# Peripherals_-_MyoSensor.net
KiCad netlist of a schematic drawn in Altium Designer
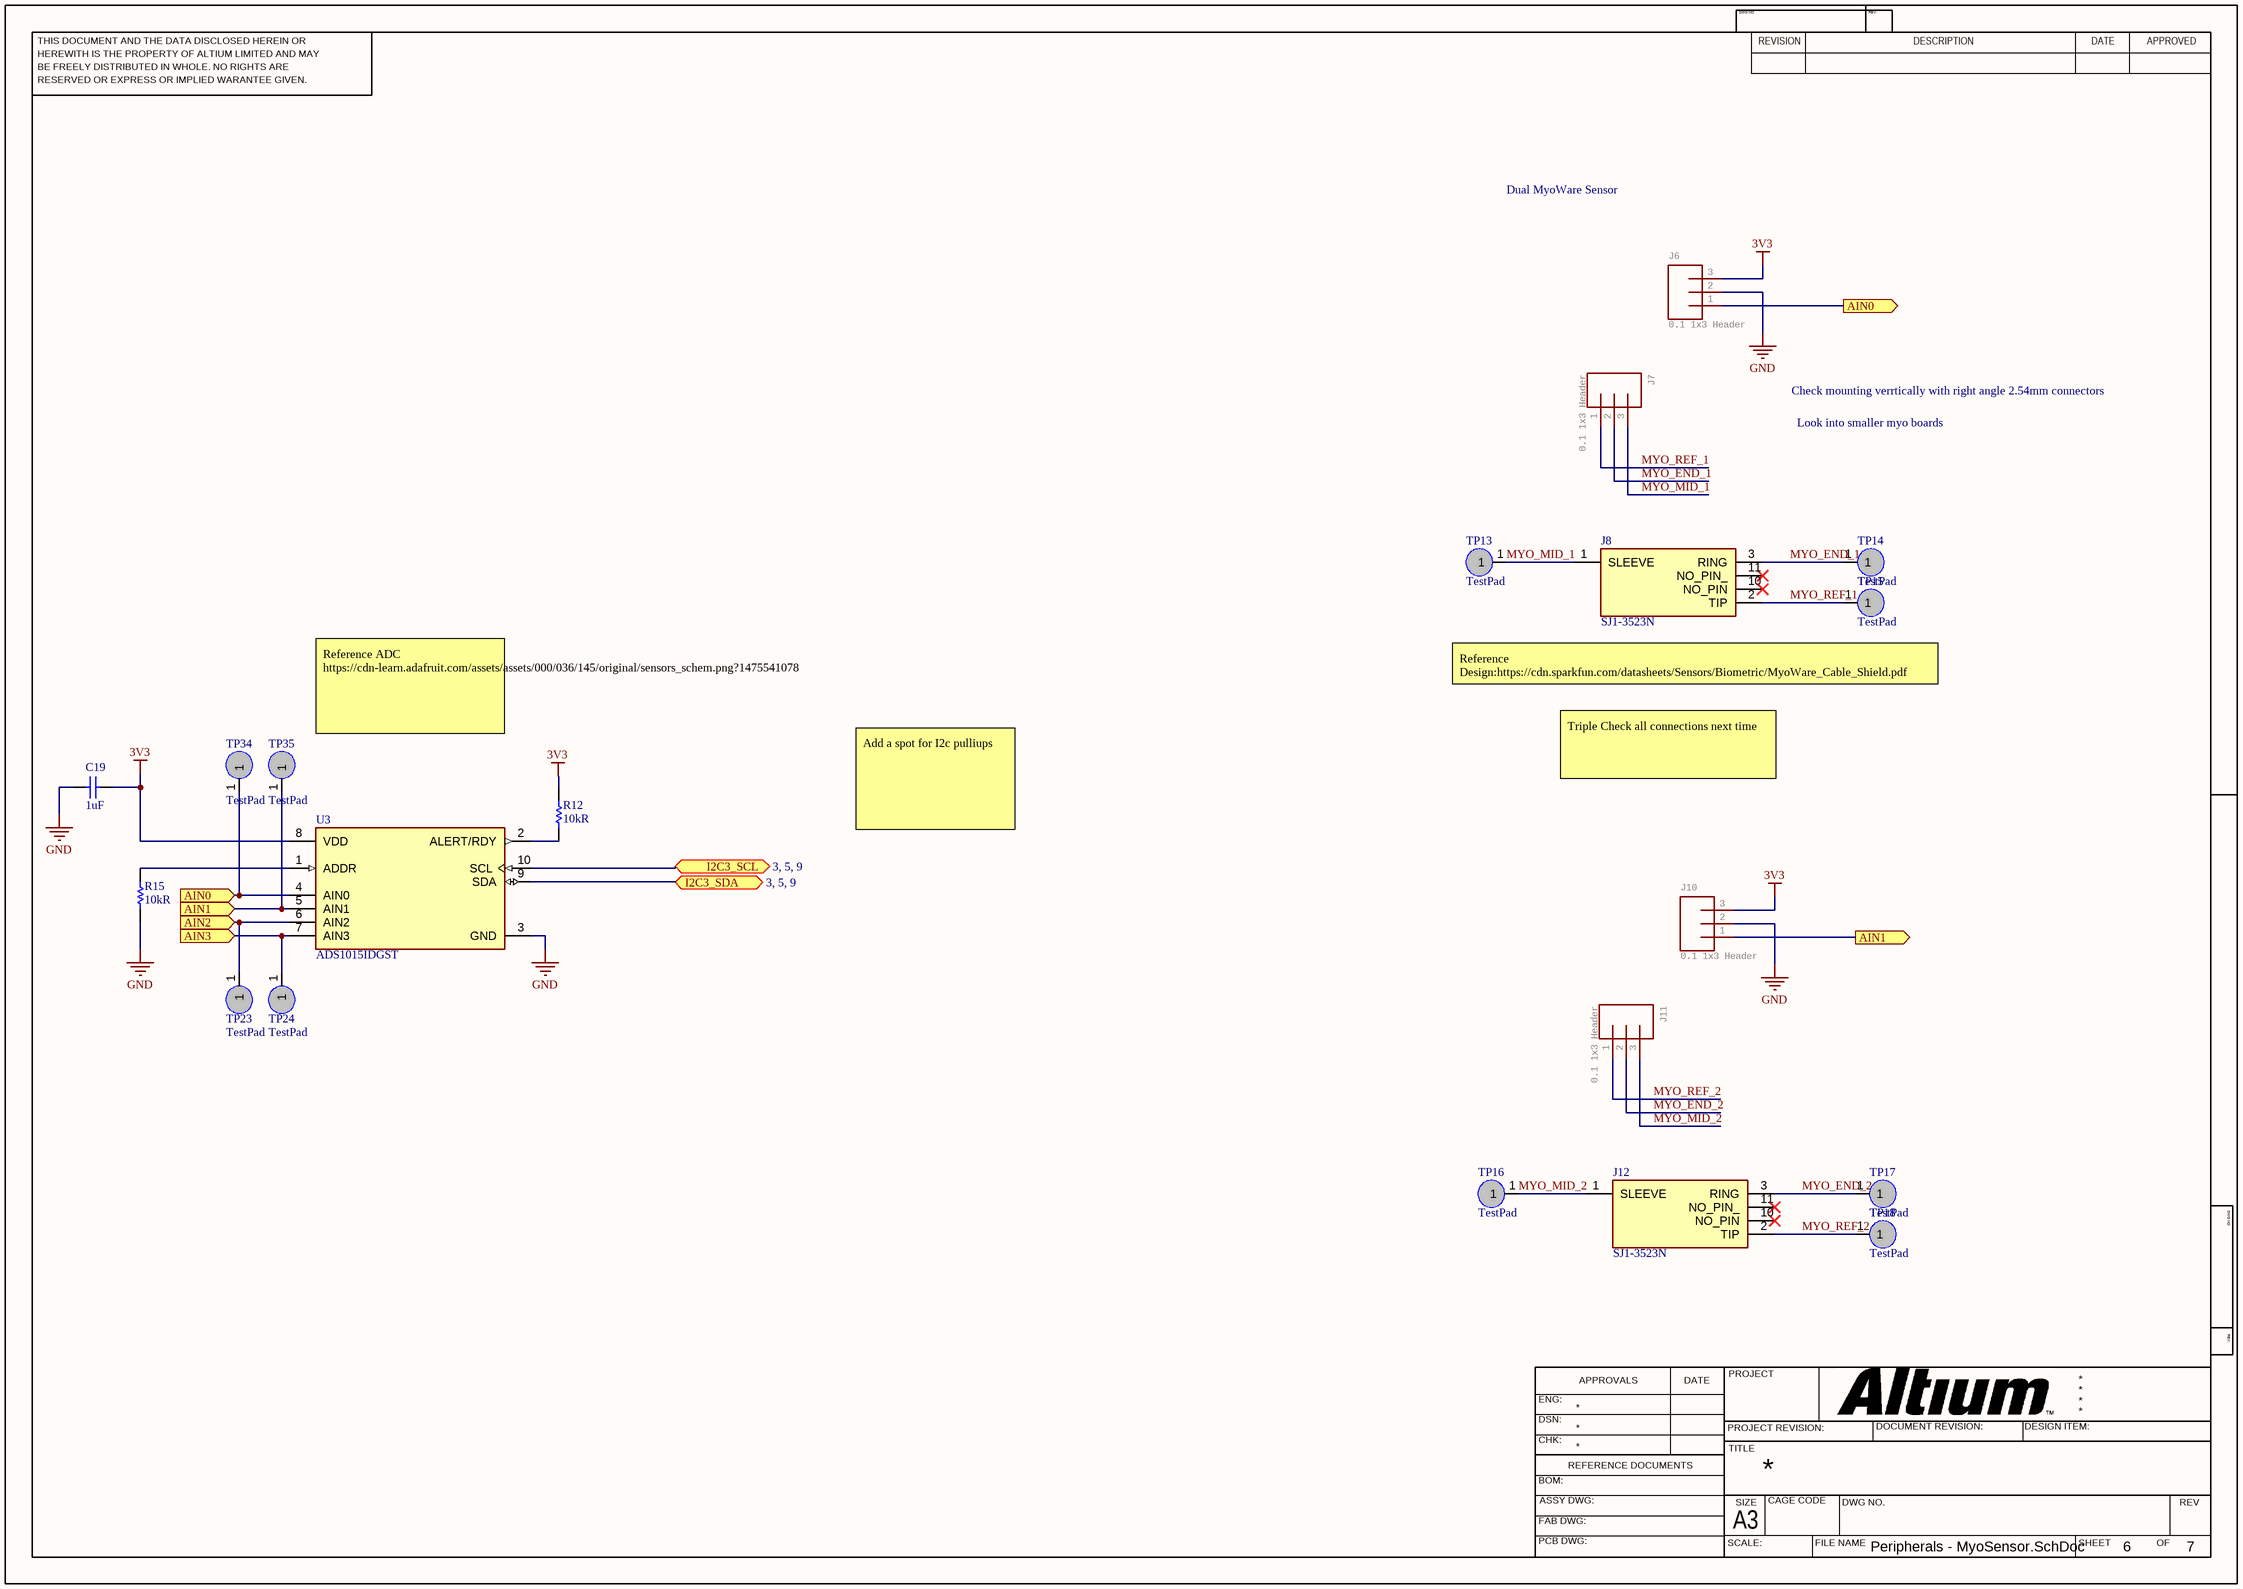
[diagram p0: Peripherals - MyoSensor.SchDoc]

(export (version "E")
  (design (tool "Eeschema 10.0.6"))
  (components
    (comp (ref "C19")
      (value "1uF")
      (footprint "CAPC2013X145X50LL20T25")
      (description "C0805C105K4PACTU")
      (fields (field (name "MANUFACTURER") "Kemet"))
      (libsource (lib "Altium Content Vault") (part "CAP"))
    )
    (comp (ref "J6")
      (value "0.1 1x3 Header")
      (footprint "1X03")
      (libsource (lib "SparkFun-Connectors.Library") (part "CONN_03"))
    )
    (comp (ref "J7")
      (value "0.1 1x3 Header")
      (footprint "1X03")
      (libsource (lib "SparkFun-Connectors.Library") (part "CONN_03"))
    )
    (comp (ref "J8")
      (value "SJ1-3523N")
      (footprint "LayoutFootprintsGoogle:SJ13523N")
      (description "Connector")
      (fields (field (name "MOUSER PART NUMBER") "490-SJ1-3523N"))
      (libsource (lib "*") (part "SJ1-3523N"))
    )
    (comp (ref "J10")
      (value "0.1 1x3 Header")
      (footprint "1X03")
      (libsource (lib "SparkFun-Connectors.Library") (part "CONN_03"))
    )
    (comp (ref "J11")
      (value "0.1 1x3 Header")
      (footprint "1X03")
      (libsource (lib "SparkFun-Connectors.Library") (part "CONN_03"))
    )
    (comp (ref "J12")
      (value "SJ1-3523N")
      (footprint "LayoutFootprintsGoogle:SJ13523N")
      (description "Connector")
      (fields (field (name "MOUSER PART NUMBER") "490-SJ1-3523N"))
      (libsource (lib "*") (part "SJ1-3523N"))
    )
    (comp (ref "R12")
      (value "10kR")
      (footprint "RESC2013X60X35NL10T20")
      (fields (field (name "MANUFACTURER") "Yageo"))
      (libsource (lib "Altium Content Vault") (part "RES-2"))
    )
    (comp (ref "R15")
      (value "10kR")
      (footprint "RESC2013X60X35NL10T20")
      (fields (field (name "MANUFACTURER") "Yageo"))
      (libsource (lib "Altium Content Vault") (part "RES-2"))
    )
    (comp (ref "TP13")
      (value "TestPad")
      (footprint "TestPad50mil")
      (libsource (lib "SchemSymbolsGoogle") (part "TestPad"))
    )
    (comp (ref "TP14")
      (value "TestPad")
      (footprint "TestPad50mil")
      (libsource (lib "SchemSymbolsGoogle") (part "TestPad"))
    )
    (comp (ref "TP15")
      (value "TestPad")
      (footprint "TestPad50mil")
      (libsource (lib "SchemSymbolsGoogle") (part "TestPad"))
    )
    (comp (ref "TP16")
      (value "TestPad")
      (footprint "TestPad50mil")
      (libsource (lib "SchemSymbolsGoogle") (part "TestPad"))
    )
    (comp (ref "TP17")
      (value "TestPad")
      (footprint "TestPad50mil")
      (libsource (lib "SchemSymbolsGoogle") (part "TestPad"))
    )
    (comp (ref "TP18")
      (value "TestPad")
      (footprint "TestPad50mil")
      (libsource (lib "SchemSymbolsGoogle") (part "TestPad"))
    )
    (comp (ref "TP23")
      (value "TestPad")
      (footprint "TestPad50mil")
      (libsource (lib "SchemSymbolsGoogle") (part "TestPad"))
    )
    (comp (ref "TP24")
      (value "TestPad")
      (footprint "TestPad50mil")
      (libsource (lib "SchemSymbolsGoogle") (part "TestPad"))
    )
    (comp (ref "TP34")
      (value "TestPad")
      (footprint "TestPad50mil")
      (libsource (lib "SchemSymbolsGoogle") (part "TestPad"))
    )
    (comp (ref "TP35")
      (value "TestPad")
      (footprint "TestPad50mil")
      (libsource (lib "SchemSymbolsGoogle") (part "TestPad"))
    )
    (comp (ref "U3")
      (value "ADS1015IDGST")
      (footprint "FP-DGS0010A-MFG")
      (description "IC ADC 12BIT SIGMA-DELTA 10VSSOP")
      (libsource (lib "Altium Content Vault") (part "0fb225032f4bd54fd540a872e776a50"))
    )
  )
  (nets
    (net (code "1") (name "/AIN0") (class "Default")
      (node (ref "J6") (pin "1") (pinfunction "1_1") (pintype "passive"))
      (node (ref "TP34") (pin "1") (pinfunction "1_1") (pintype "passive"))
      (node (ref "U3") (pin "4") (pinfunction "AIN0_4") (pintype "passive"))
    )
    (net (code "2") (name "/AIN1") (class "Default")
      (node (ref "J10") (pin "1") (pinfunction "1_1") (pintype "passive"))
      (node (ref "TP35") (pin "1") (pinfunction "1_1") (pintype "passive"))
      (node (ref "U3") (pin "5") (pinfunction "AIN1_5") (pintype "passive"))
    )
    (net (code "3") (name "/AIN2") (class "Default")
      (node (ref "TP23") (pin "1") (pinfunction "1_1") (pintype "passive"))
      (node (ref "U3") (pin "6") (pinfunction "AIN2_6") (pintype "passive"))
    )
    (net (code "4") (name "/AIN3") (class "Default")
      (node (ref "TP24") (pin "1") (pinfunction "1_1") (pintype "passive"))
      (node (ref "U3") (pin "7") (pinfunction "AIN3_7") (pintype "passive"))
    )
    (net (code "5") (name "/I2C3_SCL") (class "Default")
      (node (ref "U3") (pin "10") (pinfunction "SCL_10") (pintype "input"))
    )
    (net (code "6") (name "/I2C3_SDA") (class "Default")
      (node (ref "U3") (pin "9") (pinfunction "SDA_9") (pintype "bidirectional"))
    )
    (net (code "7") (name "/MYO_END_1") (class "Default")
      (node (ref "J7") (pin "2") (pinfunction "2_2") (pintype "passive"))
      (node (ref "J8") (pin "3") (pinfunction "RING_3") (pintype "passive"))
      (node (ref "TP14") (pin "1") (pinfunction "1_1") (pintype "passive"))
    )
    (net (code "8") (name "/MYO_END_2") (class "Default")
      (node (ref "J11") (pin "2") (pinfunction "2_2") (pintype "passive"))
      (node (ref "J12") (pin "3") (pinfunction "RING_3") (pintype "passive"))
      (node (ref "TP17") (pin "1") (pinfunction "1_1") (pintype "passive"))
    )
    (net (code "9") (name "/MYO_MID_1") (class "Default")
      (node (ref "J7") (pin "3") (pinfunction "3_3") (pintype "passive"))
      (node (ref "J8") (pin "1") (pinfunction "SLEEVE_1") (pintype "passive"))
      (node (ref "TP13") (pin "1") (pinfunction "1_1") (pintype "passive"))
    )
    (net (code "10") (name "/MYO_MID_2") (class "Default")
      (node (ref "J11") (pin "3") (pinfunction "3_3") (pintype "passive"))
      (node (ref "J12") (pin "1") (pinfunction "SLEEVE_1") (pintype "passive"))
      (node (ref "TP16") (pin "1") (pinfunction "1_1") (pintype "passive"))
    )
    (net (code "11") (name "/MYO_REF_1") (class "Default")
      (node (ref "J7") (pin "1") (pinfunction "1_1") (pintype "passive"))
      (node (ref "J8") (pin "2") (pinfunction "TIP_2") (pintype "passive"))
      (node (ref "TP15") (pin "1") (pinfunction "1_1") (pintype "passive"))
    )
    (net (code "12") (name "/MYO_REF_2") (class "Default")
      (node (ref "J11") (pin "1") (pinfunction "1_1") (pintype "passive"))
      (node (ref "J12") (pin "2") (pinfunction "TIP_2") (pintype "passive"))
      (node (ref "TP18") (pin "1") (pinfunction "1_1") (pintype "passive"))
    )
    (net (code "13") (name "3V3") (class "Default")
      (node (ref "C19") (pin "2") (pinfunction "2_2") (pintype "passive"))
      (node (ref "J10") (pin "3") (pinfunction "3_3") (pintype "passive"))
      (node (ref "J6") (pin "3") (pinfunction "3_3") (pintype "passive"))
      (node (ref "R12") (pin "2") (pinfunction "2_2") (pintype "passive"))
      (node (ref "U3") (pin "8") (pinfunction "VDD_8") (pintype "power_in"))
    )
    (net (code "14") (name "GND") (class "Default")
      (node (ref "C19") (pin "1") (pinfunction "1_1") (pintype "passive"))
      (node (ref "J10") (pin "2") (pinfunction "2_2") (pintype "passive"))
      (node (ref "J6") (pin "2") (pinfunction "2_2") (pintype "passive"))
      (node (ref "R15") (pin "1") (pinfunction "1_1") (pintype "passive"))
      (node (ref "U3") (pin "3") (pinfunction "GND_3") (pintype "power_in"))
    )
    (net (code "15") (name "Net-(U3-ADDR)") (class "Default")
      (node (ref "R15") (pin "2") (pinfunction "2_2") (pintype "passive"))
      (node (ref "U3") (pin "1") (pinfunction "ADDR_1") (pintype "input"))
    )
    (net (code "16") (name "Net-(U3-ALERT{slash}RDY)") (class "Default")
      (node (ref "R12") (pin "1") (pinfunction "1_1") (pintype "passive"))
      (node (ref "U3") (pin "2") (pinfunction "ALERT/RDY_2") (pintype "output"))
    )
    (net (code "17") (name "unconnected-(J8-NO_PIN-Pad10)") (class "Default")
      (node (ref "J8") (pin "10") (pinfunction "NO_PIN_10") (pintype "passive+no_connect"))
    )
    (net (code "18") (name "unconnected-(J8-NO_PIN_-Pad11)") (class "Default")
      (node (ref "J8") (pin "11") (pinfunction "NO_PIN__11") (pintype "passive+no_connect"))
    )
    (net (code "19") (name "unconnected-(J12-NO_PIN-Pad10)") (class "Default")
      (node (ref "J12") (pin "10") (pinfunction "NO_PIN_10") (pintype "passive+no_connect"))
    )
    (net (code "20") (name "unconnected-(J12-NO_PIN_-Pad11)") (class "Default")
      (node (ref "J12") (pin "11") (pinfunction "NO_PIN__11") (pintype "passive+no_connect"))
    )
  )
)
